# eib-64-nanoz-adapter.net
KiCad netlist of a schematic drawn in EAGLE
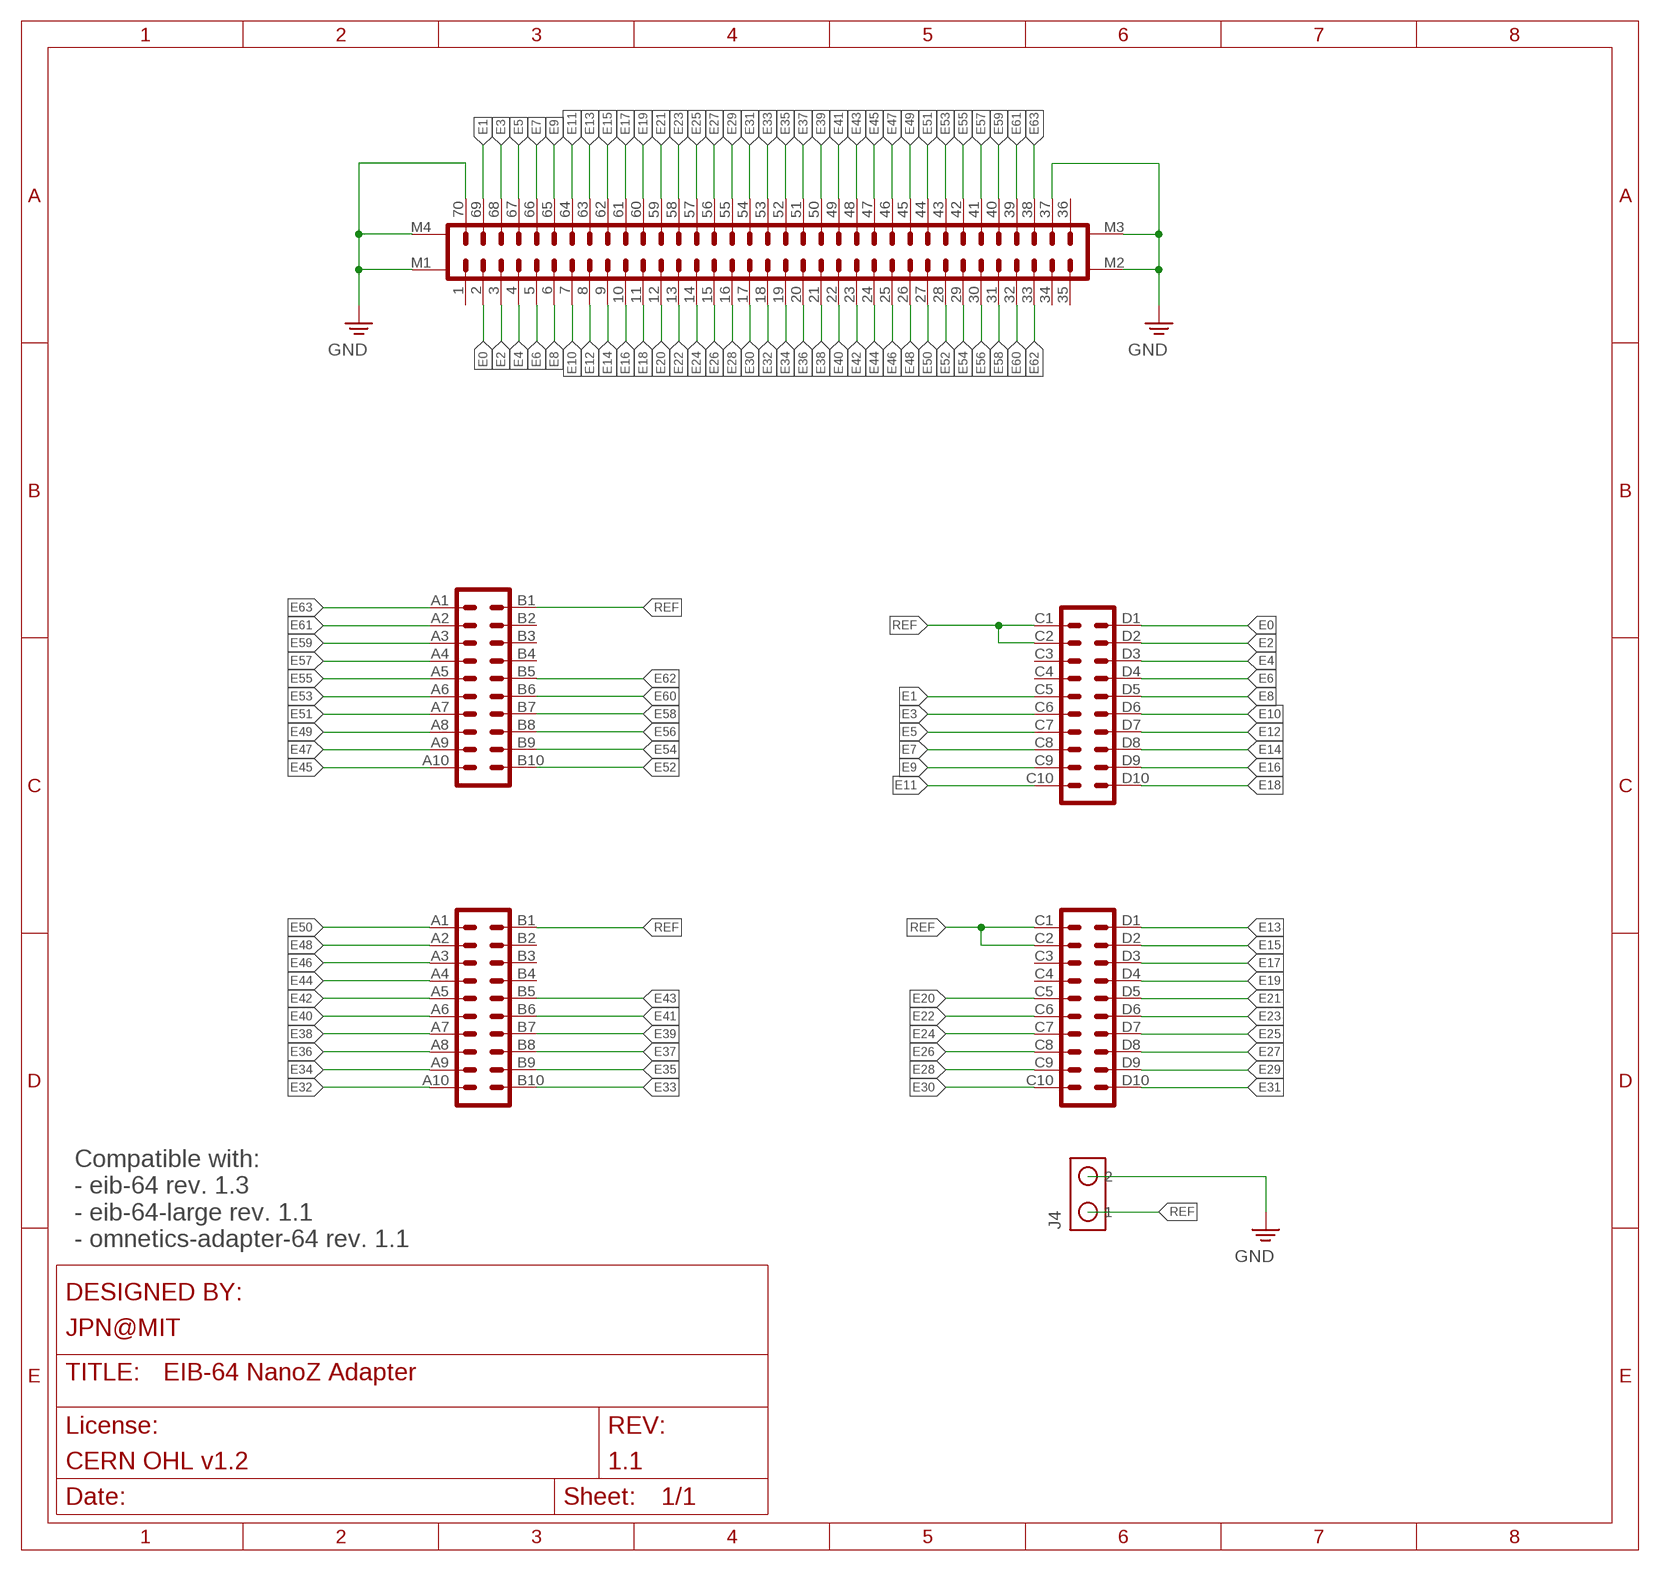
[diagram p0: schematic, sheet 1]

(export (version "E")
  (design (tool "Eeschema 10.0.6"))
  (components
    (comp (ref "J1")
      (value "DF40-REC")
      (footprint "eagle-import:DF40-70HEAD")
      (libsource (lib "eagle-import") (part "PINHD-2X35+4_DF40-70HEAD"))
    )
    (comp (ref "J2")
      (value "PINHD-4X10_MOLC-THRU")
      (footprint "eagle-import:MOLC-110-11-S-Q")
      (libsource (lib "eagle-import") (part "PINHD-4X10_MOLC-THRU"))
    )
    (comp (ref "J3")
      (value "PINHD-4X10_MOLC-THRU")
      (footprint "eagle-import:MOLC-110-11-S-Q")
      (libsource (lib "eagle-import") (part "PINHD-4X10_MOLC-THRU"))
    )
    (comp (ref "J4")
      (value "SCREW2")
      (footprint "eagle-import:SCREW2")
      (libsource (lib "eagle-import") (part "SCREW2"))
    )
  )
  (nets
    (net (code "1") (name "E0") (class "Default")
      (node (ref "J1") (pin "2") (pinfunction "2_2") (pintype "bidirectional"))
      (node (ref "J2") (pin "D1") (pinfunction "20_D1") (pintype "bidirectional"))
    )
    (net (code "2") (name "E1") (class "Default")
      (node (ref "J1") (pin "69") (pinfunction "69_69") (pintype "bidirectional"))
      (node (ref "J2") (pin "C5") (pinfunction "5_C5") (pintype "bidirectional"))
    )
    (net (code "3") (name "E2") (class "Default")
      (node (ref "J1") (pin "3") (pinfunction "3_3") (pintype "bidirectional"))
      (node (ref "J2") (pin "D2") (pinfunction "19_D2") (pintype "bidirectional"))
    )
    (net (code "4") (name "E3") (class "Default")
      (node (ref "J1") (pin "68") (pinfunction "68_68") (pintype "bidirectional"))
      (node (ref "J2") (pin "C6") (pinfunction "6_C6") (pintype "bidirectional"))
    )
    (net (code "5") (name "E4") (class "Default")
      (node (ref "J1") (pin "4") (pinfunction "4_4") (pintype "bidirectional"))
      (node (ref "J2") (pin "D3") (pinfunction "18_D3") (pintype "bidirectional"))
    )
    (net (code "6") (name "E5") (class "Default")
      (node (ref "J1") (pin "67") (pinfunction "67_67") (pintype "bidirectional"))
      (node (ref "J2") (pin "C7") (pinfunction "7_C7") (pintype "bidirectional"))
    )
    (net (code "7") (name "E6") (class "Default")
      (node (ref "J1") (pin "5") (pinfunction "5_5") (pintype "bidirectional"))
      (node (ref "J2") (pin "D4") (pinfunction "17_D4") (pintype "bidirectional"))
    )
    (net (code "8") (name "E7") (class "Default")
      (node (ref "J1") (pin "66") (pinfunction "66_66") (pintype "bidirectional"))
      (node (ref "J2") (pin "C8") (pinfunction "8_C8") (pintype "bidirectional"))
    )
    (net (code "9") (name "E8") (class "Default")
      (node (ref "J1") (pin "6") (pinfunction "6_6") (pintype "bidirectional"))
      (node (ref "J2") (pin "D5") (pinfunction "16_D5") (pintype "bidirectional"))
    )
    (net (code "10") (name "E9") (class "Default")
      (node (ref "J1") (pin "65") (pinfunction "65_65") (pintype "bidirectional"))
      (node (ref "J2") (pin "C9") (pinfunction "9_C9") (pintype "bidirectional"))
    )
    (net (code "11") (name "E10") (class "Default")
      (node (ref "J1") (pin "7") (pinfunction "7_7") (pintype "bidirectional"))
      (node (ref "J2") (pin "D6") (pinfunction "15_D6") (pintype "bidirectional"))
    )
    (net (code "12") (name "E11") (class "Default")
      (node (ref "J1") (pin "64") (pinfunction "64_64") (pintype "bidirectional"))
      (node (ref "J2") (pin "C10") (pinfunction "10_C10") (pintype "bidirectional"))
    )
    (net (code "13") (name "E12") (class "Default")
      (node (ref "J1") (pin "8") (pinfunction "8_8") (pintype "bidirectional"))
      (node (ref "J2") (pin "D7") (pinfunction "14_D7") (pintype "bidirectional"))
    )
    (net (code "14") (name "E13") (class "Default")
      (node (ref "J1") (pin "63") (pinfunction "63_63") (pintype "bidirectional"))
      (node (ref "J3") (pin "D1") (pinfunction "20_D1") (pintype "bidirectional"))
    )
    (net (code "15") (name "E14") (class "Default")
      (node (ref "J1") (pin "9") (pinfunction "9_9") (pintype "bidirectional"))
      (node (ref "J2") (pin "D8") (pinfunction "13_D8") (pintype "bidirectional"))
    )
    (net (code "16") (name "E15") (class "Default")
      (node (ref "J1") (pin "62") (pinfunction "62_62") (pintype "bidirectional"))
      (node (ref "J3") (pin "D2") (pinfunction "19_D2") (pintype "bidirectional"))
    )
    (net (code "17") (name "E16") (class "Default")
      (node (ref "J1") (pin "10") (pinfunction "10_10") (pintype "bidirectional"))
      (node (ref "J2") (pin "D9") (pinfunction "12_D9") (pintype "bidirectional"))
    )
    (net (code "18") (name "E17") (class "Default")
      (node (ref "J1") (pin "61") (pinfunction "61_61") (pintype "bidirectional"))
      (node (ref "J3") (pin "D3") (pinfunction "18_D3") (pintype "bidirectional"))
    )
    (net (code "19") (name "E18") (class "Default")
      (node (ref "J1") (pin "11") (pinfunction "11_11") (pintype "bidirectional"))
      (node (ref "J2") (pin "D10") (pinfunction "11_D10") (pintype "bidirectional"))
    )
    (net (code "20") (name "E19") (class "Default")
      (node (ref "J1") (pin "60") (pinfunction "60_60") (pintype "bidirectional"))
      (node (ref "J3") (pin "D4") (pinfunction "17_D4") (pintype "bidirectional"))
    )
    (net (code "21") (name "E20") (class "Default")
      (node (ref "J1") (pin "12") (pinfunction "12_12") (pintype "bidirectional"))
      (node (ref "J3") (pin "C5") (pinfunction "5_C5") (pintype "bidirectional"))
    )
    (net (code "22") (name "E21") (class "Default")
      (node (ref "J1") (pin "59") (pinfunction "59_59") (pintype "bidirectional"))
      (node (ref "J3") (pin "D5") (pinfunction "16_D5") (pintype "bidirectional"))
    )
    (net (code "23") (name "E22") (class "Default")
      (node (ref "J1") (pin "13") (pinfunction "13_13") (pintype "bidirectional"))
      (node (ref "J3") (pin "C6") (pinfunction "6_C6") (pintype "bidirectional"))
    )
    (net (code "24") (name "E23") (class "Default")
      (node (ref "J1") (pin "58") (pinfunction "58_58") (pintype "bidirectional"))
      (node (ref "J3") (pin "D6") (pinfunction "15_D6") (pintype "bidirectional"))
    )
    (net (code "25") (name "E24") (class "Default")
      (node (ref "J1") (pin "14") (pinfunction "14_14") (pintype "bidirectional"))
      (node (ref "J3") (pin "C7") (pinfunction "7_C7") (pintype "bidirectional"))
    )
    (net (code "26") (name "E25") (class "Default")
      (node (ref "J1") (pin "57") (pinfunction "57_57") (pintype "bidirectional"))
      (node (ref "J3") (pin "D7") (pinfunction "14_D7") (pintype "bidirectional"))
    )
    (net (code "27") (name "E26") (class "Default")
      (node (ref "J1") (pin "15") (pinfunction "15_15") (pintype "bidirectional"))
      (node (ref "J3") (pin "C8") (pinfunction "8_C8") (pintype "bidirectional"))
    )
    (net (code "28") (name "E27") (class "Default")
      (node (ref "J1") (pin "56") (pinfunction "56_56") (pintype "bidirectional"))
      (node (ref "J3") (pin "D8") (pinfunction "13_D8") (pintype "bidirectional"))
    )
    (net (code "29") (name "E28") (class "Default")
      (node (ref "J1") (pin "16") (pinfunction "16_16") (pintype "bidirectional"))
      (node (ref "J3") (pin "C9") (pinfunction "9_C9") (pintype "bidirectional"))
    )
    (net (code "30") (name "E29") (class "Default")
      (node (ref "J1") (pin "55") (pinfunction "55_55") (pintype "bidirectional"))
      (node (ref "J3") (pin "D9") (pinfunction "12_D9") (pintype "bidirectional"))
    )
    (net (code "31") (name "E30") (class "Default")
      (node (ref "J1") (pin "17") (pinfunction "17_17") (pintype "bidirectional"))
      (node (ref "J3") (pin "C10") (pinfunction "10_C10") (pintype "bidirectional"))
    )
    (net (code "32") (name "E31") (class "Default")
      (node (ref "J1") (pin "54") (pinfunction "54_54") (pintype "bidirectional"))
      (node (ref "J3") (pin "D10") (pinfunction "11_D10") (pintype "bidirectional"))
    )
    (net (code "33") (name "E32") (class "Default")
      (node (ref "J1") (pin "18") (pinfunction "18_18") (pintype "bidirectional"))
      (node (ref "J3") (pin "A10") (pinfunction "10_A10") (pintype "bidirectional"))
    )
    (net (code "34") (name "E33") (class "Default")
      (node (ref "J1") (pin "53") (pinfunction "53_53") (pintype "bidirectional"))
      (node (ref "J3") (pin "B10") (pinfunction "11_B10") (pintype "bidirectional"))
    )
    (net (code "35") (name "E34") (class "Default")
      (node (ref "J1") (pin "19") (pinfunction "19_19") (pintype "bidirectional"))
      (node (ref "J3") (pin "A9") (pinfunction "9_A9") (pintype "bidirectional"))
    )
    (net (code "36") (name "E35") (class "Default")
      (node (ref "J1") (pin "52") (pinfunction "52_52") (pintype "bidirectional"))
      (node (ref "J3") (pin "B9") (pinfunction "12_B9") (pintype "bidirectional"))
    )
    (net (code "37") (name "E36") (class "Default")
      (node (ref "J1") (pin "20") (pinfunction "20_20") (pintype "bidirectional"))
      (node (ref "J3") (pin "A8") (pinfunction "8_A8") (pintype "bidirectional"))
    )
    (net (code "38") (name "E37") (class "Default")
      (node (ref "J1") (pin "51") (pinfunction "51_51") (pintype "bidirectional"))
      (node (ref "J3") (pin "B8") (pinfunction "13_B8") (pintype "bidirectional"))
    )
    (net (code "39") (name "E38") (class "Default")
      (node (ref "J1") (pin "21") (pinfunction "21_21") (pintype "bidirectional"))
      (node (ref "J3") (pin "A7") (pinfunction "7_A7") (pintype "bidirectional"))
    )
    (net (code "40") (name "E39") (class "Default")
      (node (ref "J1") (pin "50") (pinfunction "50_50") (pintype "bidirectional"))
      (node (ref "J3") (pin "B7") (pinfunction "14_B7") (pintype "bidirectional"))
    )
    (net (code "41") (name "E40") (class "Default")
      (node (ref "J1") (pin "22") (pinfunction "22_22") (pintype "bidirectional"))
      (node (ref "J3") (pin "A6") (pinfunction "6_A6") (pintype "bidirectional"))
    )
    (net (code "42") (name "E41") (class "Default")
      (node (ref "J1") (pin "49") (pinfunction "49_49") (pintype "bidirectional"))
      (node (ref "J3") (pin "B6") (pinfunction "15_B6") (pintype "bidirectional"))
    )
    (net (code "43") (name "E42") (class "Default")
      (node (ref "J1") (pin "23") (pinfunction "23_23") (pintype "bidirectional"))
      (node (ref "J3") (pin "A5") (pinfunction "5_A5") (pintype "bidirectional"))
    )
    (net (code "44") (name "E43") (class "Default")
      (node (ref "J1") (pin "48") (pinfunction "48_48") (pintype "bidirectional"))
      (node (ref "J3") (pin "B5") (pinfunction "16_B5") (pintype "bidirectional"))
    )
    (net (code "45") (name "E44") (class "Default")
      (node (ref "J1") (pin "24") (pinfunction "24_24") (pintype "bidirectional"))
      (node (ref "J3") (pin "A4") (pinfunction "4_A4") (pintype "bidirectional"))
    )
    (net (code "46") (name "E45") (class "Default")
      (node (ref "J1") (pin "47") (pinfunction "47_47") (pintype "bidirectional"))
      (node (ref "J2") (pin "A10") (pinfunction "10_A10") (pintype "bidirectional"))
    )
    (net (code "47") (name "E46") (class "Default")
      (node (ref "J1") (pin "25") (pinfunction "25_25") (pintype "bidirectional"))
      (node (ref "J3") (pin "A3") (pinfunction "3_A3") (pintype "bidirectional"))
    )
    (net (code "48") (name "E47") (class "Default")
      (node (ref "J1") (pin "46") (pinfunction "46_46") (pintype "bidirectional"))
      (node (ref "J2") (pin "A9") (pinfunction "9_A9") (pintype "bidirectional"))
    )
    (net (code "49") (name "E48") (class "Default")
      (node (ref "J1") (pin "26") (pinfunction "26_26") (pintype "bidirectional"))
      (node (ref "J3") (pin "A2") (pinfunction "2_A2") (pintype "bidirectional"))
    )
    (net (code "50") (name "E49") (class "Default")
      (node (ref "J1") (pin "45") (pinfunction "45_45") (pintype "bidirectional"))
      (node (ref "J2") (pin "A8") (pinfunction "8_A8") (pintype "bidirectional"))
    )
    (net (code "51") (name "E50") (class "Default")
      (node (ref "J1") (pin "27") (pinfunction "27_27") (pintype "bidirectional"))
      (node (ref "J3") (pin "A1") (pinfunction "1_A1") (pintype "bidirectional"))
    )
    (net (code "52") (name "E51") (class "Default")
      (node (ref "J1") (pin "44") (pinfunction "44_44") (pintype "bidirectional"))
      (node (ref "J2") (pin "A7") (pinfunction "7_A7") (pintype "bidirectional"))
    )
    (net (code "53") (name "E52") (class "Default")
      (node (ref "J1") (pin "28") (pinfunction "28_28") (pintype "bidirectional"))
      (node (ref "J2") (pin "B10") (pinfunction "11_B10") (pintype "bidirectional"))
    )
    (net (code "54") (name "E53") (class "Default")
      (node (ref "J1") (pin "43") (pinfunction "43_43") (pintype "bidirectional"))
      (node (ref "J2") (pin "A6") (pinfunction "6_A6") (pintype "bidirectional"))
    )
    (net (code "55") (name "E54") (class "Default")
      (node (ref "J1") (pin "29") (pinfunction "29_29") (pintype "bidirectional"))
      (node (ref "J2") (pin "B9") (pinfunction "12_B9") (pintype "bidirectional"))
    )
    (net (code "56") (name "E55") (class "Default")
      (node (ref "J1") (pin "42") (pinfunction "42_42") (pintype "bidirectional"))
      (node (ref "J2") (pin "A5") (pinfunction "5_A5") (pintype "bidirectional"))
    )
    (net (code "57") (name "E56") (class "Default")
      (node (ref "J1") (pin "30") (pinfunction "30_30") (pintype "bidirectional"))
      (node (ref "J2") (pin "B8") (pinfunction "13_B8") (pintype "bidirectional"))
    )
    (net (code "58") (name "E57") (class "Default")
      (node (ref "J1") (pin "41") (pinfunction "41_41") (pintype "bidirectional"))
      (node (ref "J2") (pin "A4") (pinfunction "4_A4") (pintype "bidirectional"))
    )
    (net (code "59") (name "E58") (class "Default")
      (node (ref "J1") (pin "31") (pinfunction "31_31") (pintype "bidirectional"))
      (node (ref "J2") (pin "B7") (pinfunction "14_B7") (pintype "bidirectional"))
    )
    (net (code "60") (name "E59") (class "Default")
      (node (ref "J1") (pin "40") (pinfunction "40_40") (pintype "bidirectional"))
      (node (ref "J2") (pin "A3") (pinfunction "3_A3") (pintype "bidirectional"))
    )
    (net (code "61") (name "E60") (class "Default")
      (node (ref "J1") (pin "32") (pinfunction "32_32") (pintype "bidirectional"))
      (node (ref "J2") (pin "B6") (pinfunction "15_B6") (pintype "bidirectional"))
    )
    (net (code "62") (name "E61") (class "Default")
      (node (ref "J1") (pin "39") (pinfunction "39_39") (pintype "bidirectional"))
      (node (ref "J2") (pin "A2") (pinfunction "2_A2") (pintype "bidirectional"))
    )
    (net (code "63") (name "E62") (class "Default")
      (node (ref "J1") (pin "33") (pinfunction "33_33") (pintype "bidirectional"))
      (node (ref "J2") (pin "B5") (pinfunction "16_B5") (pintype "bidirectional"))
    )
    (net (code "64") (name "E63") (class "Default")
      (node (ref "J1") (pin "38") (pinfunction "38_38") (pintype "bidirectional"))
      (node (ref "J2") (pin "A1") (pinfunction "1_A1") (pintype "bidirectional"))
    )
    (net (code "65") (name "GND") (class "Default")
      (node (ref "J1") (pin "37") (pinfunction "37_37") (pintype "bidirectional"))
      (node (ref "J1") (pin "70") (pinfunction "70_70") (pintype "bidirectional"))
      (node (ref "J1") (pin "M1") (pinfunction "M1_M1") (pintype "bidirectional"))
      (node (ref "J1") (pin "M2") (pinfunction "M2_M2") (pintype "bidirectional"))
      (node (ref "J1") (pin "M3") (pinfunction "M3_M3") (pintype "bidirectional"))
      (node (ref "J1") (pin "M4") (pinfunction "M4_M4") (pintype "bidirectional"))
      (node (ref "J4") (pin "P$2") (pinfunction "2_P$2") (pintype "passive"))
    )
    (net (code "66") (name "REF") (class "Default")
      (node (ref "J2") (pin "B1") (pinfunction "20_B1") (pintype "bidirectional"))
      (node (ref "J2") (pin "C1") (pinfunction "1_C1") (pintype "bidirectional"))
      (node (ref "J2") (pin "C2") (pinfunction "2_C2") (pintype "bidirectional"))
      (node (ref "J3") (pin "B1") (pinfunction "20_B1") (pintype "bidirectional"))
      (node (ref "J3") (pin "C1") (pinfunction "1_C1") (pintype "bidirectional"))
      (node (ref "J3") (pin "C2") (pinfunction "2_C2") (pintype "bidirectional"))
      (node (ref "J4") (pin "P$1") (pinfunction "1_P$1") (pintype "passive"))
    )
    (net (code "67") (name "unconnected-(J1-Pad1)") (class "Default")
      (node (ref "J1") (pin "1") (pinfunction "1_1") (pintype "bidirectional"))
    )
    (net (code "68") (name "unconnected-(J1-Pad34)") (class "Default")
      (node (ref "J1") (pin "34") (pinfunction "34_34") (pintype "bidirectional"))
    )
    (net (code "69") (name "unconnected-(J1-Pad35)") (class "Default")
      (node (ref "J1") (pin "35") (pinfunction "35_35") (pintype "bidirectional"))
    )
    (net (code "70") (name "unconnected-(J1-Pad36)") (class "Default")
      (node (ref "J1") (pin "36") (pinfunction "36_36") (pintype "bidirectional"))
    )
    (net (code "71") (name "unconnected-(J2A-17-PadB4)") (class "Default")
      (node (ref "J2") (pin "B4") (pinfunction "17_B4") (pintype "bidirectional"))
    )
    (net (code "72") (name "unconnected-(J2A-18-PadB3)") (class "Default")
      (node (ref "J2") (pin "B3") (pinfunction "18_B3") (pintype "bidirectional"))
    )
    (net (code "73") (name "unconnected-(J2A-19-PadB2)") (class "Default")
      (node (ref "J2") (pin "B2") (pinfunction "19_B2") (pintype "bidirectional"))
    )
    (net (code "74") (name "unconnected-(J2B-3-PadC3)") (class "Default")
      (node (ref "J2") (pin "C3") (pinfunction "3_C3") (pintype "bidirectional"))
    )
    (net (code "75") (name "unconnected-(J2B-4-PadC4)") (class "Default")
      (node (ref "J2") (pin "C4") (pinfunction "4_C4") (pintype "bidirectional"))
    )
    (net (code "76") (name "unconnected-(J3A-17-PadB4)") (class "Default")
      (node (ref "J3") (pin "B4") (pinfunction "17_B4") (pintype "bidirectional"))
    )
    (net (code "77") (name "unconnected-(J3A-18-PadB3)") (class "Default")
      (node (ref "J3") (pin "B3") (pinfunction "18_B3") (pintype "bidirectional"))
    )
    (net (code "78") (name "unconnected-(J3A-19-PadB2)") (class "Default")
      (node (ref "J3") (pin "B2") (pinfunction "19_B2") (pintype "bidirectional"))
    )
    (net (code "79") (name "unconnected-(J3B-3-PadC3)") (class "Default")
      (node (ref "J3") (pin "C3") (pinfunction "3_C3") (pintype "bidirectional"))
    )
    (net (code "80") (name "unconnected-(J3B-4-PadC4)") (class "Default")
      (node (ref "J3") (pin "C4") (pinfunction "4_C4") (pintype "bidirectional"))
    )
  )
)
